# EEPROM_Temp_LEDs.net
KiCad netlist of a schematic drawn in Altium Designer
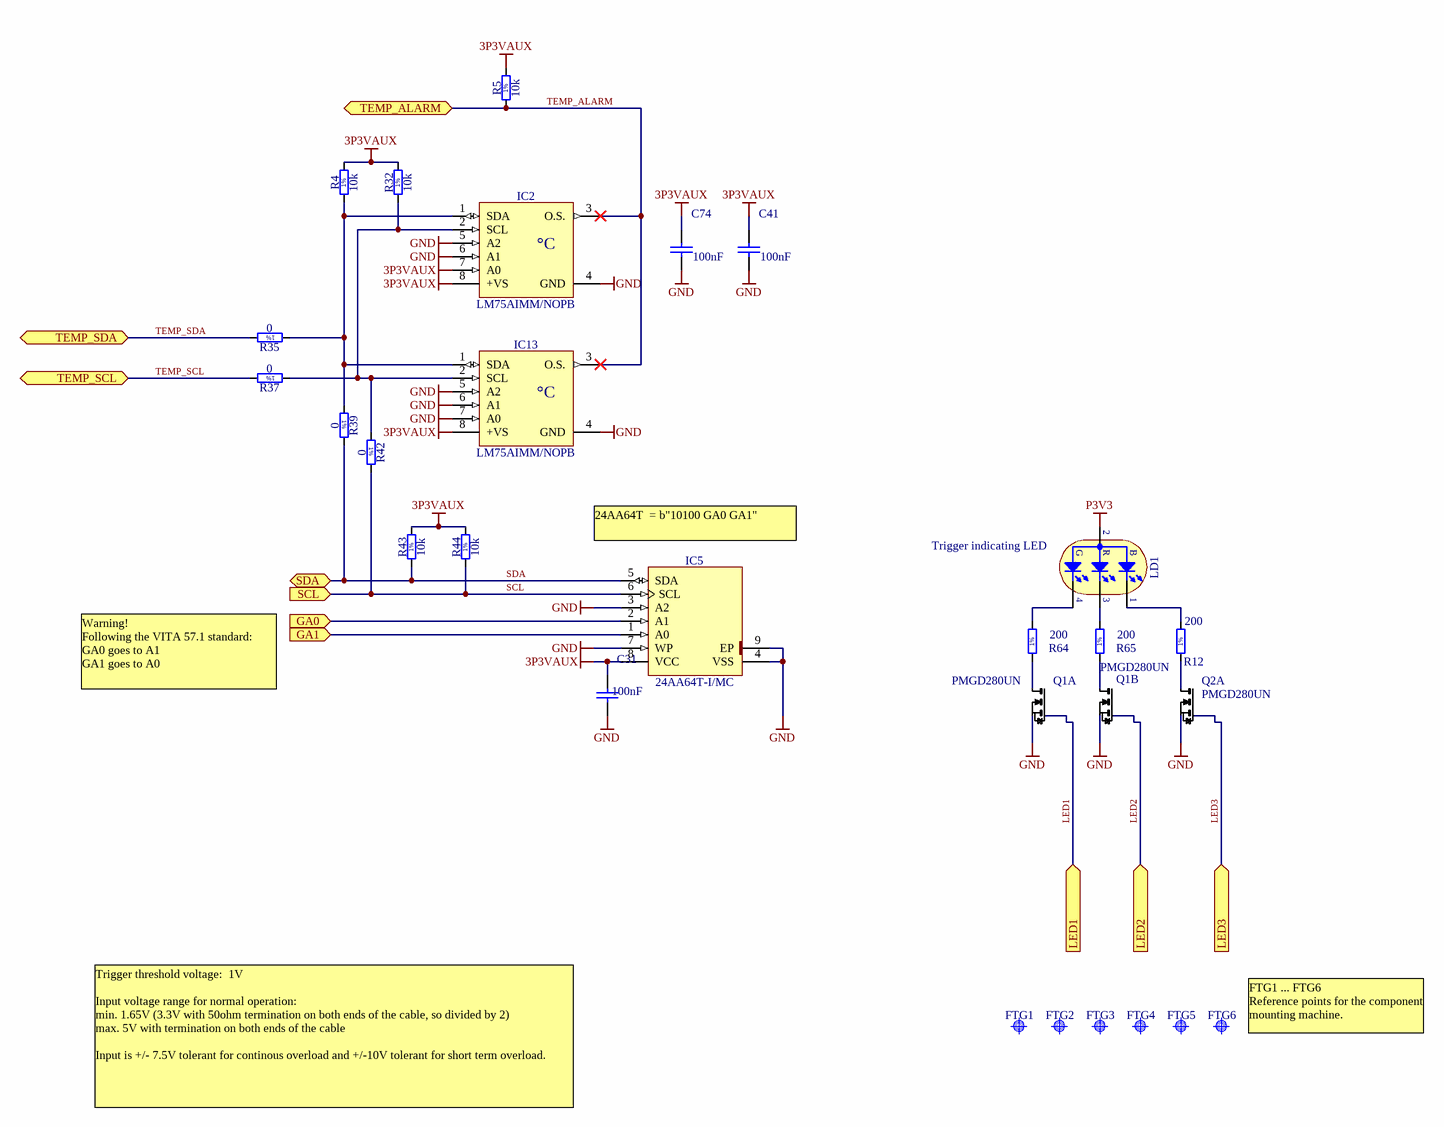
[diagram p0: EEPROM_Temp_LEDs.SchDoc]

(export (version "E")
  (design (tool "Eeschema 10.0.6"))
  (components
    (comp (ref "C31")
      (value "100nF")
      (footprint "CAPC0603X33N")
      (description "Non-polarised capacitor")
      (fields
        (field (name "PART NUMBER") "CC0201_100NF_6.3V_10%_X5R")
        (field (name "VOLTAGE") "6.3V")
        (field (name "AUTHOR") "CERN DEM JLC")
      )
      (libsource (lib "Capacitors") (part "Capacitor - non polarized"))
    )
    (comp (ref "C41")
      (value "100nF")
      (footprint "CAPC0603X33N")
      (description "Non-polarised capacitor")
      (fields
        (field (name "PART NUMBER") "CC0201_100NF_6.3V_10%_X5R")
        (field (name "VOLTAGE") "6.3V")
        (field (name "AUTHOR") "CERN DEM JLC")
      )
      (libsource (lib "Capacitors") (part "Capacitor - non polarized"))
    )
    (comp (ref "C74")
      (value "100nF")
      (footprint "CAPC0603X33N")
      (description "Non-polarised capacitor")
      (fields
        (field (name "PART NUMBER") "CC0201_100NF_6.3V_10%_X5R")
        (field (name "VOLTAGE") "6.3V")
        (field (name "AUTHOR") "CERN DEM JLC")
      )
      (libsource (lib "Capacitors") (part "Capacitor - non polarized"))
    )
    (comp (ref "FTG1")
      (value "Use only in PCB")
      (footprint "FIDUCIAL_TOP_S100-200")
      (description "Fiducial Target")
      (fields (field (name "PART NUMBER") "FIDUCIAL_TARGET_S100-200") (field (name "AUTHOR") "CERN DEM JLC"))
      (libsource (lib "Eletro-mechanical") (part "Fiducial Target"))
    )
    (comp (ref "FTG2")
      (value "Use only in PCB")
      (footprint "FIDUCIAL_TOP_S100-200")
      (description "Fiducial Target")
      (fields (field (name "PART NUMBER") "FIDUCIAL_TARGET_S100-200") (field (name "AUTHOR") "CERN DEM JLC"))
      (libsource (lib "Eletro-mechanical") (part "Fiducial Target"))
    )
    (comp (ref "FTG3")
      (value "Use only in PCB")
      (footprint "FIDUCIAL_TOP_S100-200")
      (description "Fiducial Target")
      (fields (field (name "PART NUMBER") "FIDUCIAL_TARGET_S100-200") (field (name "AUTHOR") "CERN DEM JLC"))
      (libsource (lib "Eletro-mechanical") (part "Fiducial Target"))
    )
    (comp (ref "FTG4")
      (value "Use only in PCB")
      (footprint "FIDUCIAL_TOP_S100-200")
      (description "Fiducial Target")
      (fields (field (name "PART NUMBER") "FIDUCIAL_TARGET_S100-200") (field (name "AUTHOR") "CERN DEM JLC"))
      (libsource (lib "Eletro-mechanical") (part "Fiducial Target"))
    )
    (comp (ref "FTG5")
      (value "Use only in PCB")
      (footprint "FIDUCIAL_TOP_S100-200")
      (description "Fiducial Target")
      (fields (field (name "PART NUMBER") "FIDUCIAL_TARGET_S100-200") (field (name "AUTHOR") "CERN DEM JLC"))
      (libsource (lib "Eletro-mechanical") (part "Fiducial Target"))
    )
    (comp (ref "FTG6")
      (value "Use only in PCB")
      (footprint "FIDUCIAL_TOP_S100-200")
      (description "Fiducial Target")
      (fields (field (name "PART NUMBER") "FIDUCIAL_TARGET_S100-200") (field (name "AUTHOR") "CERN DEM JLC"))
      (libsource (lib "Eletro-mechanical") (part "Fiducial Target"))
    )
    (comp (ref "IC2")
      (value "LM75AIMM/NOPB")
      (footprint "SOP65P490X109-8N")
      (description "Digital Temperature Sensor and Thermal Watchdog with Two-Wire Interface")
      (fields (field (name "MANUFACTURER") "TEXAS INSTRUMENTS") (field (name "AUTHOR") "CERN DEM JLC"))
      (libsource (lib "ICs And Semiconductors") (part "LM75"))
    )
    (comp (ref "IC5")
      (value "24AA64T-I/MC")
      (footprint "SON50P300X200X100-9N-S175X155")
      (description "1.7-5.5V 64K I2C Serial EEPROM")
      (fields (field (name "MANUFACTURER") "MICROCHIP TECHNOLOGY") (field (name "AUTHOR") "CERN DEM JLC"))
      (libsource (lib "ICs And Semiconductors") (part "24AA64T-I/MC"))
    )
    (comp (ref "IC13")
      (value "LM75AIMM/NOPB")
      (footprint "SOP65P490X109-8N")
      (description "Digital Temperature Sensor and Thermal Watchdog with Two-Wire Interface")
      (fields (field (name "MANUFACTURER") "TEXAS INSTRUMENTS") (field (name "AUTHOR") "CERN DEM JLC"))
      (libsource (lib "ICs And Semiconductors") (part "LM75"))
    )
    (comp (ref "LD1")
      (value "Blue/Red/Green")
      (footprint "LED_AVAGO_HSMF-C113")
      (description "Tricolor LEDs 1 Cathode Blue, 2 Common Anode, 3 Cathode Red, 4 Cathode Green")
      (fields
        (field (name "PART NUMBER") "LED_AVAGO_HSMF-C113")
        (field (name "MANUFACTURER") "AVAGO TECHNOLOGIES")
        (field (name "AUTHOR") "CERN DEM JLC")
      )
      (libsource (lib "ICs And Semiconductors") (part "LED Blue-Red-Green 1CB_2AC_3CR_4CG"))
    )
    (comp (ref "Q1")
      (value "PMGD280UN")
      (footprint "SOT-363")
      (description "Dual NMOS 20V,08.A, 340mR, Vt=0.7V")
      (libsource (lib "LIBRARY_SCH") (part "Q_PMGD280UN"))
    )
    (comp (ref "Q2")
      (value "PMGD280UN")
      (footprint "SOT-363")
      (description "Dual NMOS 20V,08.A, 340mR, Vt=0.7V")
      (libsource (lib "LIBRARY_SCH") (part "Q_PMGD280UN"))
    )
    (comp (ref "R4")
      (value "10k")
      (footprint "RESC1005X40N")
      (description "Resistor - 1%")
      (fields
        (field (name "PART NUMBER") "R0402_10K_1%_0.0625W_100PPM")
        (field (name "POWER") "0.0625W")
        (field (name "AUTHOR") "CERN DEM JLC")
      )
      (libsource (lib "Resistors") (part "Resistor - 1%"))
    )
    (comp (ref "R5")
      (value "10k")
      (footprint "RESC1005X40N")
      (description "Resistor - 1%")
      (fields
        (field (name "PART NUMBER") "R0402_10K_1%_0.0625W_100PPM")
        (field (name "POWER") "0.0625W")
        (field (name "AUTHOR") "CERN DEM JLC")
      )
      (libsource (lib "Resistors") (part "Resistor - 1%"))
    )
    (comp (ref "R12")
      (value "200")
      (footprint "RESC1005X40N")
      (description "Resistor - 1%")
      (fields
        (field (name "PART NUMBER") "R0402_200R_1%_0.0625W_100PPM")
        (field (name "POWER") "0.0625W")
        (field (name "AUTHOR") "CERN DEM JLC")
      )
      (libsource (lib "Resistors") (part "Resistor - 1%"))
    )
    (comp (ref "R32")
      (value "10k")
      (footprint "RESC1005X40N")
      (description "Resistor - 1%")
      (fields
        (field (name "PART NUMBER") "R0402_10K_1%_0.0625W_100PPM")
        (field (name "POWER") "0.0625W")
        (field (name "AUTHOR") "CERN DEM JLC")
      )
      (libsource (lib "Resistors") (part "Resistor - 1%"))
    )
    (comp (ref "R35")
      (value "0")
      (footprint "RESC1005X40N")
      (description "Resistor - 1%")
      (fields
        (field (name "PART NUMBER") "R0402_0R_JUMPER")
        (field (name "MANUFACTURER") "GENERIC")
        (field (name "AUTHOR") "CERN DEM JLC")
      )
      (libsource (lib "Resistors") (part "Resistor - 1%"))
    )
    (comp (ref "R37")
      (value "0")
      (footprint "RESC1005X40N")
      (description "Resistor - 1%")
      (fields
        (field (name "PART NUMBER") "R0402_0R_JUMPER")
        (field (name "MANUFACTURER") "GENERIC")
        (field (name "AUTHOR") "CERN DEM JLC")
      )
      (libsource (lib "Resistors") (part "Resistor - 1%"))
    )
    (comp (ref "R39")
      (value "0")
      (footprint "RESC1005X40N")
      (description "Resistor - 1%")
      (fields
        (field (name "PART NUMBER") "R0402_0R_JUMPER")
        (field (name "MANUFACTURER") "GENERIC")
        (field (name "AUTHOR") "CERN DEM JLC")
      )
      (libsource (lib "Resistors") (part "Resistor - 1%"))
    )
    (comp (ref "R42")
      (value "0")
      (footprint "RESC1005X40N")
      (description "Resistor - 1%")
      (fields
        (field (name "PART NUMBER") "R0402_0R_JUMPER")
        (field (name "MANUFACTURER") "GENERIC")
        (field (name "AUTHOR") "CERN DEM JLC")
      )
      (libsource (lib "Resistors") (part "Resistor - 1%"))
    )
    (comp (ref "R43")
      (value "10k")
      (footprint "RESC1005X40N")
      (description "Resistor - 1%")
      (fields
        (field (name "PART NUMBER") "R0402_10K_1%_0.0625W_100PPM")
        (field (name "POWER") "0.0625W")
        (field (name "AUTHOR") "CERN DEM JLC")
      )
      (libsource (lib "Resistors") (part "Resistor - 1%"))
    )
    (comp (ref "R44")
      (value "10k")
      (footprint "RESC1005X40N")
      (description "Resistor - 1%")
      (fields
        (field (name "PART NUMBER") "R0402_10K_1%_0.0625W_100PPM")
        (field (name "POWER") "0.0625W")
        (field (name "AUTHOR") "CERN DEM JLC")
      )
      (libsource (lib "Resistors") (part "Resistor - 1%"))
    )
    (comp (ref "R64")
      (value "200")
      (footprint "RESC1005X40N")
      (description "Resistor - 1%")
      (fields
        (field (name "PART NUMBER") "R0402_200R_1%_0.0625W_100PPM")
        (field (name "POWER") "0.0625W")
        (field (name "AUTHOR") "CERN DEM JLC")
      )
      (libsource (lib "Resistors") (part "Resistor - 1%"))
    )
    (comp (ref "R65")
      (value "200")
      (footprint "RESC1005X40N")
      (description "Resistor - 1%")
      (fields
        (field (name "PART NUMBER") "R0402_200R_1%_0.0625W_100PPM")
        (field (name "POWER") "0.0625W")
        (field (name "AUTHOR") "CERN DEM JLC")
      )
      (libsource (lib "Resistors") (part "Resistor - 1%"))
    )
  )
  (nets
    (net (code "1") (name "/GA0") (class "Default")
      (node (ref "IC5") (pin "2") (pinfunction "A1_2") (pintype "input"))
    )
    (net (code "2") (name "/GA1") (class "Default")
      (node (ref "IC5") (pin "1") (pinfunction "A0_1") (pintype "input"))
    )
    (net (code "3") (name "/LED1") (class "Default")
      (node (ref "Q1") (pin "2") (pinfunction "G1_2") (pintype "input"))
    )
    (net (code "4") (name "/LED2") (class "Default")
      (node (ref "Q1") (pin "5") (pinfunction "G1_5") (pintype "input"))
    )
    (net (code "5") (name "/LED3") (class "Default")
      (node (ref "Q2") (pin "2") (pinfunction "G1_2") (pintype "input"))
    )
    (net (code "6") (name "/SCL") (class "Default")
      (node (ref "IC5") (pin "6") (pinfunction "SCL_6") (pintype "input"))
      (node (ref "R42") (pin "2") (pinfunction "2_2") (pintype "passive"))
      (node (ref "R44") (pin "1") (pinfunction "1_1") (pintype "passive"))
    )
    (net (code "7") (name "/SDA") (class "Default")
      (node (ref "IC5") (pin "5") (pinfunction "SDA_5") (pintype "bidirectional"))
      (node (ref "R39") (pin "2") (pinfunction "2_2") (pintype "passive"))
      (node (ref "R43") (pin "1") (pinfunction "1_1") (pintype "passive"))
    )
    (net (code "8") (name "/TEMP_ALARM") (class "Default")
      (node (ref "IC13") (pin "3") (pinfunction "O.S._3") (pintype "output"))
      (node (ref "IC2") (pin "3") (pinfunction "O.S._3") (pintype "output"))
      (node (ref "R5") (pin "1") (pinfunction "1_1") (pintype "passive"))
    )
    (net (code "9") (name "/TEMP_SCL") (class "Default")
      (node (ref "R37") (pin "2") (pinfunction "2_2") (pintype "passive"))
    )
    (net (code "10") (name "/TEMP_SDA") (class "Default")
      (node (ref "R35") (pin "2") (pinfunction "2_2") (pintype "passive"))
    )
    (net (code "11") (name "3P3VAUX") (class "Default")
      (node (ref "C31") (pin "1") (pinfunction "1_1") (pintype "passive"))
      (node (ref "C41") (pin "1") (pinfunction "1_1") (pintype "passive"))
      (node (ref "C74") (pin "1") (pinfunction "1_1") (pintype "passive"))
      (node (ref "IC13") (pin "8") (pinfunction "+VS_8") (pintype "power_in"))
      (node (ref "IC2") (pin "7") (pinfunction "A0_7") (pintype "input"))
      (node (ref "IC2") (pin "8") (pinfunction "+VS_8") (pintype "power_in"))
      (node (ref "IC5") (pin "8") (pinfunction "VCC_8") (pintype "power_in"))
      (node (ref "R32") (pin "2") (pinfunction "2_2") (pintype "passive"))
      (node (ref "R4") (pin "2") (pinfunction "2_2") (pintype "passive"))
      (node (ref "R43") (pin "2") (pinfunction "2_2") (pintype "passive"))
      (node (ref "R44") (pin "2") (pinfunction "2_2") (pintype "passive"))
      (node (ref "R5") (pin "2") (pinfunction "2_2") (pintype "passive"))
    )
    (net (code "12") (name "GND") (class "Default")
      (node (ref "C31") (pin "2") (pinfunction "2_2") (pintype "passive"))
      (node (ref "C41") (pin "2") (pinfunction "2_2") (pintype "passive"))
      (node (ref "C74") (pin "2") (pinfunction "2_2") (pintype "passive"))
      (node (ref "IC13") (pin "4") (pinfunction "GND_4") (pintype "power_in"))
      (node (ref "IC13") (pin "5") (pinfunction "A2_5") (pintype "input"))
      (node (ref "IC13") (pin "6") (pinfunction "A1_6") (pintype "input"))
      (node (ref "IC13") (pin "7") (pinfunction "A0_7") (pintype "input"))
      (node (ref "IC2") (pin "4") (pinfunction "GND_4") (pintype "power_in"))
      (node (ref "IC2") (pin "5") (pinfunction "A2_5") (pintype "input"))
      (node (ref "IC2") (pin "6") (pinfunction "A1_6") (pintype "input"))
      (node (ref "IC5") (pin "3") (pinfunction "A2_3") (pintype "input"))
      (node (ref "IC5") (pin "4") (pinfunction "VSS_4") (pintype "power_in"))
      (node (ref "IC5") (pin "7") (pinfunction "WP_7") (pintype "input"))
      (node (ref "IC5") (pin "9") (pinfunction "EP_9") (pintype "power_in"))
      (node (ref "Q1") (pin "1") (pinfunction "S1_1") (pintype "open_emitter"))
      (node (ref "Q1") (pin "4") (pinfunction "S1_4") (pintype "open_emitter"))
      (node (ref "Q2") (pin "1") (pinfunction "S1_1") (pintype "open_emitter"))
    )
    (net (code "13") (name "Net-(IC13-SCL)") (class "Default")
      (node (ref "IC13") (pin "2") (pinfunction "SCL_2") (pintype "input"))
      (node (ref "IC2") (pin "2") (pinfunction "SCL_2") (pintype "input"))
      (node (ref "R32") (pin "1") (pinfunction "1_1") (pintype "passive"))
      (node (ref "R37") (pin "1") (pinfunction "1_1") (pintype "passive"))
      (node (ref "R42") (pin "1") (pinfunction "1_1") (pintype "passive"))
    )
    (net (code "14") (name "Net-(IC13-SDA)") (class "Default")
      (node (ref "IC13") (pin "1") (pinfunction "SDA_1") (pintype "bidirectional"))
      (node (ref "IC2") (pin "1") (pinfunction "SDA_1") (pintype "bidirectional"))
      (node (ref "R35") (pin "1") (pinfunction "1_1") (pintype "passive"))
      (node (ref "R39") (pin "1") (pinfunction "1_1") (pintype "passive"))
      (node (ref "R4") (pin "1") (pinfunction "1_1") (pintype "passive"))
    )
    (net (code "15") (name "Net-(LD1-CB)") (class "Default")
      (node (ref "LD1") (pin "1") (pinfunction "CB_1") (pintype "passive"))
      (node (ref "R12") (pin "2") (pinfunction "2_2") (pintype "passive"))
    )
    (net (code "16") (name "Net-(LD1-CG)") (class "Default")
      (node (ref "LD1") (pin "4") (pinfunction "CG_4") (pintype "passive"))
      (node (ref "R64") (pin "2") (pinfunction "2_2") (pintype "passive"))
    )
    (net (code "17") (name "Net-(LD1-CR)") (class "Default")
      (node (ref "LD1") (pin "3") (pinfunction "CR_3") (pintype "passive"))
      (node (ref "R65") (pin "2") (pinfunction "2_2") (pintype "passive"))
    )
    (net (code "18") (name "Net-(Q1A-D1)") (class "Default")
      (node (ref "Q1") (pin "3") (pinfunction "D1_3") (pintype "open_collector"))
      (node (ref "R64") (pin "1") (pinfunction "1_1") (pintype "passive"))
    )
    (net (code "19") (name "Net-(Q1B-D1)") (class "Default")
      (node (ref "Q1") (pin "6") (pinfunction "D1_6") (pintype "open_collector"))
      (node (ref "R65") (pin "1") (pinfunction "1_1") (pintype "passive"))
    )
    (net (code "20") (name "Net-(Q2A-D1)") (class "Default")
      (node (ref "Q2") (pin "3") (pinfunction "D1_3") (pintype "open_collector"))
      (node (ref "R12") (pin "1") (pinfunction "1_1") (pintype "passive"))
    )
    (net (code "21") (name "P3V3") (class "Default")
      (node (ref "LD1") (pin "2") (pinfunction "AC_2") (pintype "passive"))
    )
  )
)
